# MicroMod_Processor_STM32WB5MMG.net
KiCad netlist of a schematic drawn in EAGLE
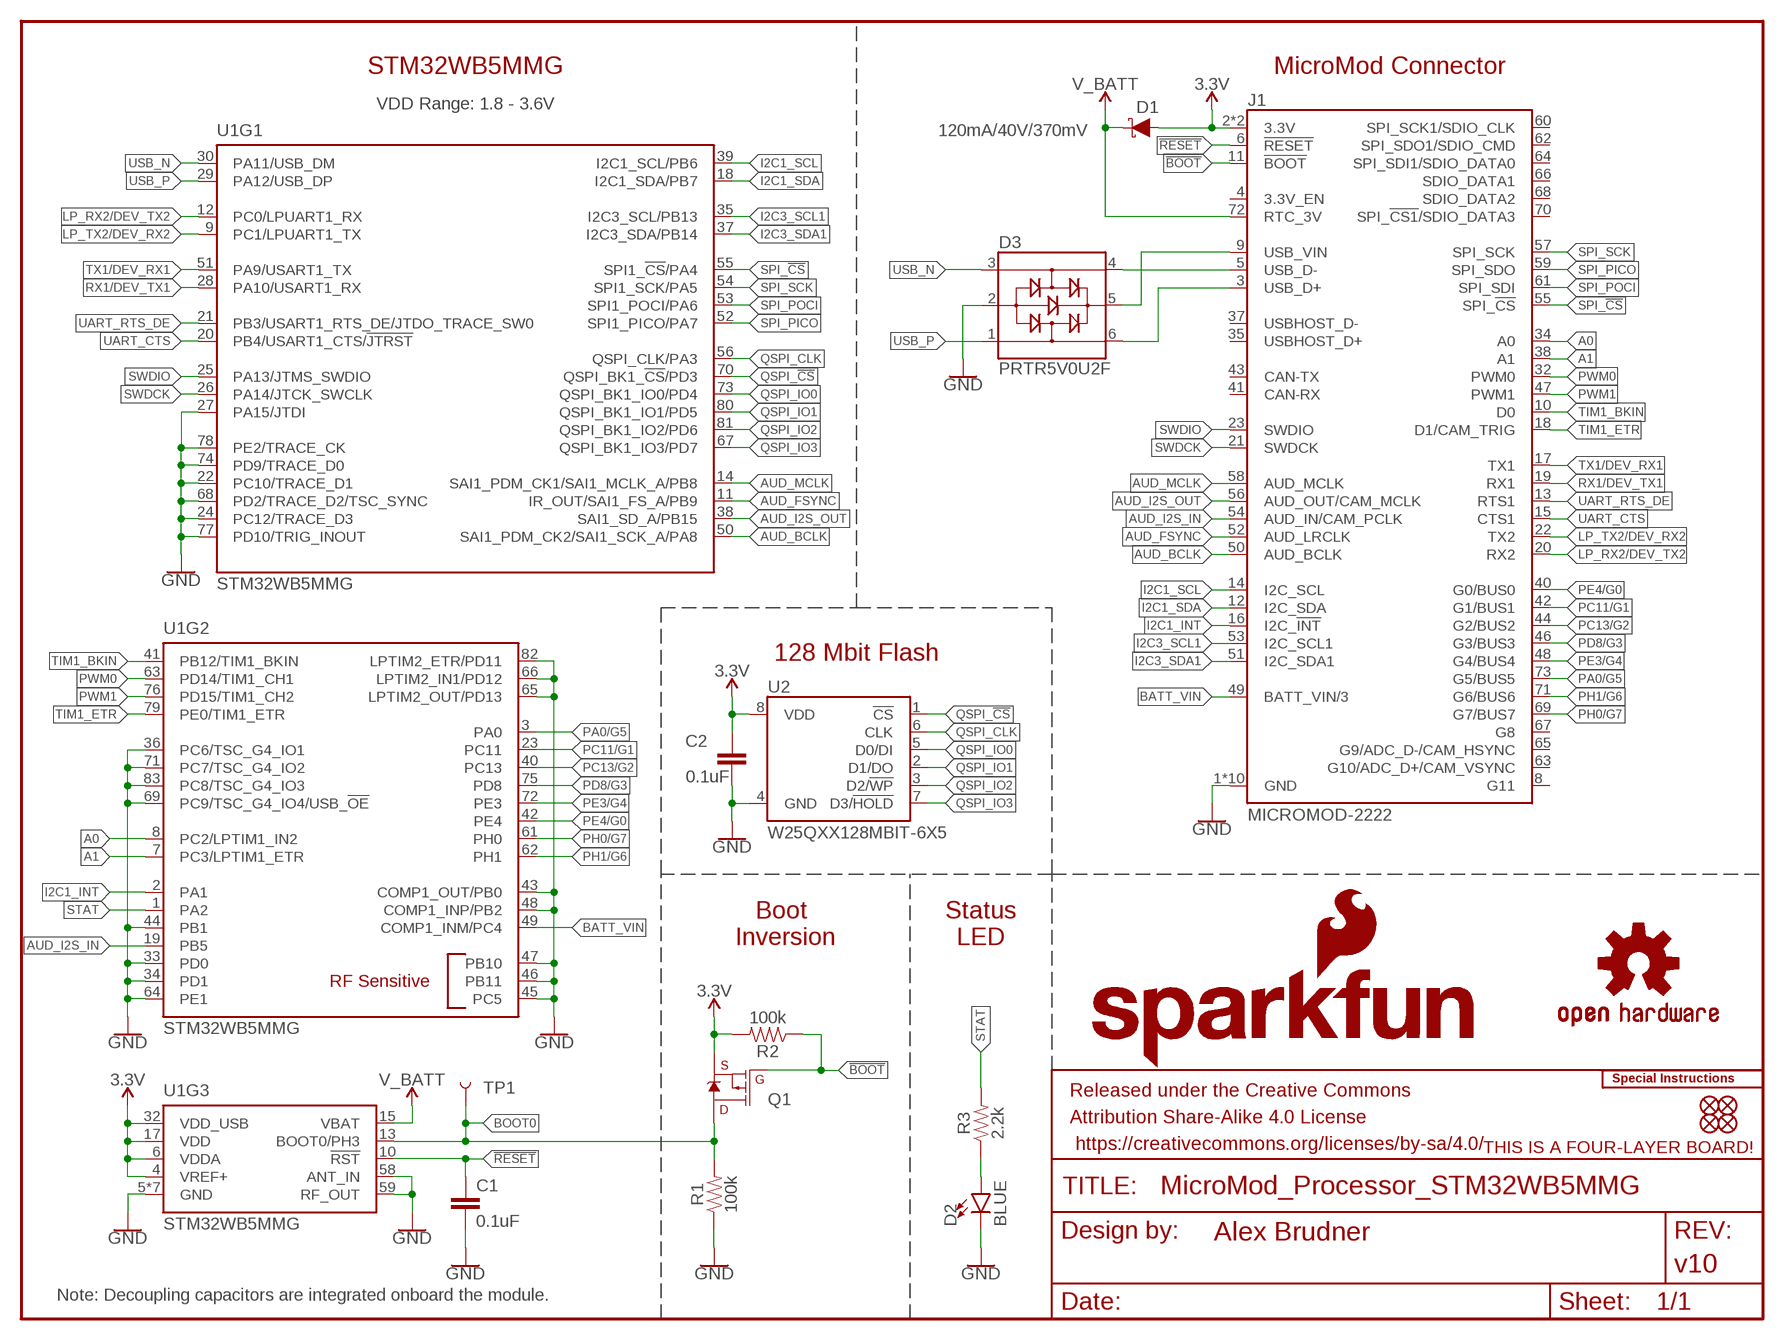
[diagram p0: schematic, sheet 1]

(export (version "E")
  (design (tool "Eeschema 10.0.6"))
  (components
    (comp (ref "C1")
      (value "0.1uF")
      (footprint "eagle-import:0402-TIGHT")
      (libsource (lib "eagle-import") (part "0.1UF-0402T-10V-10%-X7R"))
    )
    (comp (ref "C2")
      (value "0.1uF")
      (footprint "eagle-import:0402-TIGHT")
      (libsource (lib "eagle-import") (part "0.1UF-0402T-10V-10%-X7R"))
    )
    (comp (ref "D1")
      (value "120mA/40V/370mV")
      (footprint "eagle-import:SOD-523")
      (libsource (lib "eagle-import") (part "DIODE-SCHOTTKY-RB751S40"))
    )
    (comp (ref "D2")
      (value "BLUE")
      (footprint "eagle-import:LED-0603")
      (libsource (lib "eagle-import") (part "LED-BLUE0603"))
    )
    (comp (ref "D3")
      (value "PRTR5V0U2F")
      (footprint "eagle-import:SOT886")
      (libsource (lib "eagle-import") (part "PRTR5V0U2F"))
    )
    (comp (ref "FD1")
      (value "FIDUCIALUFIDUCIAL")
      (footprint "eagle-import:FIDUCIAL-MICRO")
      (libsource (lib "eagle-import") (part "FIDUCIALUFIDUCIAL"))
    )
    (comp (ref "FD2")
      (value "FIDUCIALUFIDUCIAL")
      (footprint "eagle-import:FIDUCIAL-MICRO")
      (libsource (lib "eagle-import") (part "FIDUCIALUFIDUCIAL"))
    )
    (comp (ref "FD3")
      (value "FIDUCIALUFIDUCIAL")
      (footprint "eagle-import:FIDUCIAL-MICRO")
      (libsource (lib "eagle-import") (part "FIDUCIALUFIDUCIAL"))
    )
    (comp (ref "FD4")
      (value "FIDUCIALUFIDUCIAL")
      (footprint "eagle-import:FIDUCIAL-MICRO")
      (libsource (lib "eagle-import") (part "FIDUCIALUFIDUCIAL"))
    )
    (comp (ref "FRAME2")
      (value "FRAME-LETTER")
      (footprint "eagle-import:CREATIVE_COMMONS")
      (fields (field (name "DESIGNER") "Alex Brudner") (field (name "REV") "v10"))
      (libsource (lib "eagle-import") (part "FRAME-LETTER"))
    )
    (comp (ref "J1")
      (value "MICROMOD-2222")
      (footprint "eagle-import:M.2-CARD-E-22")
      (libsource (lib "eagle-import") (part "MICROMOD-2222"))
    )
    (comp (ref "LOGO1")
      (value "FOUR_LAYER_WARNING")
      (footprint "eagle-import:FOUR_LAYER_WARNING")
      (libsource (lib "eagle-import") (part "FOUR_LAYER_WARNING"))
    )
    (comp (ref "LOGO2")
      (value "OSHW-LOGOMINI")
      (footprint "eagle-import:OSHW-LOGO-MINI")
      (libsource (lib "eagle-import") (part "OSHW-LOGOMINI"))
    )
    (comp (ref "LOGO3")
      (value "SFE_LOGO_NAME_FLAME.1_INCH")
      (footprint "eagle-import:SFE_LOGO_NAME_FLAME_.1")
      (libsource (lib "eagle-import") (part "SFE_LOGO_NAME_FLAME.1_INCH"))
    )
    (comp (ref "LOGO4")
      (value "SPECIAL_INSTRUCTIONS-ORDERING")
      (footprint "eagle-import:ORDERING_INSTRUCTIONS")
      (libsource (lib "eagle-import") (part "SPECIAL_INSTRUCTIONS-ORDERING"))
    )
    (comp (ref "Q1")
      (value "20V/4.2A/52mΩ/1.4W")
      (footprint "eagle-import:SOT23-3")
      (libsource (lib "eagle-import") (part "MOSFET_PCH-DMG2305UX-7"))
    )
    (comp (ref "R1")
      (value "100k")
      (footprint "eagle-import:0402-TIGHT")
      (libsource (lib "eagle-import") (part "100KOHM-0402T-1/16W-1%"))
    )
    (comp (ref "R2")
      (value "100k")
      (footprint "eagle-import:0402-TIGHT")
      (libsource (lib "eagle-import") (part "100KOHM-0402T-1/16W-1%"))
    )
    (comp (ref "R3")
      (value "2.2k")
      (footprint "eagle-import:0402-TIGHT")
      (libsource (lib "eagle-import") (part "2.2KOHM-0402T-1/16W-1%"))
    )
    (comp (ref "TP1")
      (value "TEST-POINT3")
      (footprint "eagle-import:PAD.03X.03")
      (libsource (lib "eagle-import") (part "TEST-POINT3"))
    )
    (comp (ref "U1")
      (value "STM32WB5MMG")
      (footprint "eagle-import:SIP-LGA86")
      (libsource (lib "eagle-import") (part "STM32WB5MMG_LOGICAL"))
    )
    (comp (ref "U2")
      (value "W25QXX128MBIT-6X5")
      (footprint "eagle-import:WSON-8-6X5")
      (libsource (lib "eagle-import") (part "W25QXX128MBIT-6X5"))
    )
  )
  (nets
    (net (code "1") (name "/QSPI_~{CS}") (class "Default")
      (node (ref "U1") (pin "70") (pinfunction "QSPI_BK1_~{CS}/PD3_70") (pintype "bidirectional"))
      (node (ref "U2") (pin "1") (pinfunction "~{CS}_1") (pintype "bidirectional"))
    )
    (net (code "2") (name "/SPI_~{CS}") (class "Default")
      (node (ref "J1") (pin "55") (pinfunction "SPI_~{CS}_55") (pintype "bidirectional"))
      (node (ref "U1") (pin "55") (pinfunction "SPI1_~{CS}/PA4_55") (pintype "bidirectional"))
    )
    (net (code "3") (name "/~{BOOT}") (class "Default")
      (node (ref "J1") (pin "11") (pinfunction "~{BOOT}_11") (pintype "bidirectional"))
      (node (ref "Q1") (pin "1") (pinfunction "G_1") (pintype "bidirectional"))
      (node (ref "R2") (pin "1") (pinfunction "1_1") (pintype "passive"))
    )
    (net (code "4") (name "/~{RESET}") (class "Default")
      (node (ref "C1") (pin "1") (pinfunction "1_1") (pintype "passive"))
      (node (ref "J1") (pin "6") (pinfunction "~{RESET}_6") (pintype "bidirectional"))
      (node (ref "U1") (pin "10") (pinfunction "~{RST}_10") (pintype "bidirectional"))
    )
    (net (code "5") (name "3.3V") (class "Default")
      (node (ref "C2") (pin "1") (pinfunction "1_1") (pintype "passive"))
      (node (ref "D1") (pin "A") (pinfunction "A_A") (pintype "passive"))
      (node (ref "J1") (pin "2") (pinfunction "3.3V_2") (pintype "bidirectional"))
      (node (ref "J1") (pin "74") (pinfunction "3.3V_74") (pintype "bidirectional"))
      (node (ref "Q1") (pin "2") (pinfunction "S_2") (pintype "bidirectional"))
      (node (ref "R2") (pin "2") (pinfunction "2_2") (pintype "passive"))
      (node (ref "U1") (pin "17") (pinfunction "VDD_17") (pintype "bidirectional"))
      (node (ref "U1") (pin "32") (pinfunction "VDD_USB_32") (pintype "bidirectional"))
      (node (ref "U1") (pin "4") (pinfunction "VREF+_4") (pintype "bidirectional"))
      (node (ref "U1") (pin "6") (pinfunction "VDDA_6") (pintype "bidirectional"))
      (node (ref "U2") (pin "8") (pinfunction "VDD_8") (pintype "bidirectional"))
    )
    (net (code "6") (name "A0") (class "Default")
      (node (ref "J1") (pin "34") (pinfunction "A0_34") (pintype "bidirectional"))
      (node (ref "U1") (pin "8") (pinfunction "PC2/LPTIM1_IN2_8") (pintype "bidirectional"))
    )
    (net (code "7") (name "A1") (class "Default")
      (node (ref "J1") (pin "38") (pinfunction "A1_38") (pintype "bidirectional"))
      (node (ref "U1") (pin "7") (pinfunction "PC3/LPTIM1_ETR_7") (pintype "bidirectional"))
    )
    (net (code "8") (name "AUD_BCLK") (class "Default")
      (node (ref "J1") (pin "50") (pinfunction "AUD_BCLK_50") (pintype "bidirectional"))
      (node (ref "U1") (pin "50") (pinfunction "SAI1_PDM_CK2/SAI1_SCK_A/PA8_50") (pintype "bidirectional"))
    )
    (net (code "9") (name "AUD_FSYNC") (class "Default")
      (node (ref "J1") (pin "52") (pinfunction "AUD_LRCLK_52") (pintype "bidirectional"))
      (node (ref "U1") (pin "11") (pinfunction "IR_OUT/SAI1_FS_A/PB9_11") (pintype "bidirectional"))
    )
    (net (code "10") (name "AUD_I2S_IN") (class "Default")
      (node (ref "J1") (pin "54") (pinfunction "AUD_IN/CAM_PCLK_54") (pintype "bidirectional"))
      (node (ref "U1") (pin "19") (pinfunction "PB5_19") (pintype "bidirectional"))
    )
    (net (code "11") (name "AUD_I2S_OUT") (class "Default")
      (node (ref "J1") (pin "56") (pinfunction "AUD_OUT/CAM_MCLK_56") (pintype "bidirectional"))
      (node (ref "U1") (pin "38") (pinfunction "SAI1_SD_A/PB15_38") (pintype "bidirectional"))
    )
    (net (code "12") (name "AUD_MCLK") (class "Default")
      (node (ref "J1") (pin "58") (pinfunction "AUD_MCLK_58") (pintype "bidirectional"))
      (node (ref "U1") (pin "14") (pinfunction "SAI1_PDM_CK1/SAI1_MCLK_A/PB8_14") (pintype "bidirectional"))
    )
    (net (code "13") (name "BATT_VIN") (class "Default")
      (node (ref "J1") (pin "49") (pinfunction "BATT_VIN/3_49") (pintype "bidirectional"))
      (node (ref "U1") (pin "49") (pinfunction "COMP1_INM/PC4_49") (pintype "bidirectional"))
    )
    (net (code "14") (name "BOOT0") (class "Default")
      (node (ref "Q1") (pin "3") (pinfunction "D_3") (pintype "bidirectional"))
      (node (ref "R1") (pin "2") (pinfunction "2_2") (pintype "passive"))
      (node (ref "TP1") (pin "1") (pinfunction "1_1") (pintype "bidirectional"))
      (node (ref "U1") (pin "13") (pinfunction "BOOT0/PH3_13") (pintype "bidirectional"))
    )
    (net (code "15") (name "GND") (class "Default")
      (node (ref "C1") (pin "2") (pinfunction "2_2") (pintype "passive"))
      (node (ref "C2") (pin "2") (pinfunction "2_2") (pintype "passive"))
      (node (ref "D2") (pin "C") (pinfunction "C_C") (pintype "passive"))
      (node (ref "D3") (pin "2") (pinfunction "2_2") (pintype "power_in"))
      (node (ref "J1") (pin "1") (pinfunction "GND_1") (pintype "bidirectional"))
      (node (ref "J1") (pin "33") (pinfunction "GND_33") (pintype "bidirectional"))
      (node (ref "J1") (pin "36") (pinfunction "GND_36") (pintype "bidirectional"))
      (node (ref "J1") (pin "39") (pinfunction "GND_39") (pintype "bidirectional"))
      (node (ref "J1") (pin "45") (pinfunction "GND_45") (pintype "bidirectional"))
      (node (ref "J1") (pin "7") (pinfunction "GND_7") (pintype "bidirectional"))
      (node (ref "J1") (pin "75") (pinfunction "GND_75") (pintype "bidirectional"))
      (node (ref "J1") (pin "GND1") (pinfunction "GND_GND1") (pintype "bidirectional"))
      (node (ref "J1") (pin "GND2") (pinfunction "GND_GND2") (pintype "bidirectional"))
      (node (ref "J1") (pin "GND3") (pinfunction "GND_GND3") (pintype "bidirectional"))
      (node (ref "R1") (pin "1") (pinfunction "1_1") (pintype "passive"))
      (node (ref "U1") (pin "16") (pinfunction "GND_16") (pintype "bidirectional"))
      (node (ref "U1") (pin "22") (pinfunction "PC10/TRACE_D1_22") (pintype "bidirectional"))
      (node (ref "U1") (pin "24") (pinfunction "PC12/TRACE_D3_24") (pintype "bidirectional"))
      (node (ref "U1") (pin "27") (pinfunction "PA15/JTDI_27") (pintype "bidirectional"))
      (node (ref "U1") (pin "31") (pinfunction "GND_31") (pintype "bidirectional"))
      (node (ref "U1") (pin "33") (pinfunction "PD0_33") (pintype "bidirectional"))
      (node (ref "U1") (pin "34") (pinfunction "PD1_34") (pintype "bidirectional"))
      (node (ref "U1") (pin "36") (pinfunction "PC6/TSC_G4_IO1_36") (pintype "bidirectional"))
      (node (ref "U1") (pin "43") (pinfunction "COMP1_OUT/PB0_43") (pintype "bidirectional"))
      (node (ref "U1") (pin "44") (pinfunction "PB1_44") (pintype "bidirectional"))
      (node (ref "U1") (pin "45") (pinfunction "PC5_45") (pintype "bidirectional"))
      (node (ref "U1") (pin "46") (pinfunction "PB11_46") (pintype "bidirectional"))
      (node (ref "U1") (pin "47") (pinfunction "PB10_47") (pintype "bidirectional"))
      (node (ref "U1") (pin "48") (pinfunction "COMP1_INP/PB2_48") (pintype "bidirectional"))
      (node (ref "U1") (pin "5") (pinfunction "GND_5") (pintype "bidirectional"))
      (node (ref "U1") (pin "57") (pinfunction "GND_57") (pintype "bidirectional"))
      (node (ref "U1") (pin "58") (pinfunction "ANT_IN_58") (pintype "bidirectional"))
      (node (ref "U1") (pin "59") (pinfunction "RF_OUT_59") (pintype "bidirectional"))
      (node (ref "U1") (pin "60") (pinfunction "GND_60") (pintype "bidirectional"))
      (node (ref "U1") (pin "64") (pinfunction "PE1_64") (pintype "bidirectional"))
      (node (ref "U1") (pin "65") (pinfunction "LPTIM2_OUT/PD13_65") (pintype "bidirectional"))
      (node (ref "U1") (pin "66") (pinfunction "LPTIM2_IN1/PD12_66") (pintype "bidirectional"))
      (node (ref "U1") (pin "68") (pinfunction "PD2/TRACE_D2/TSC_SYNC_68") (pintype "bidirectional"))
      (node (ref "U1") (pin "69") (pinfunction "PC9/TSC_G4_IO4/USB_~{OE}_69") (pintype "bidirectional"))
      (node (ref "U1") (pin "71") (pinfunction "PC7/TSC_G4_IO2_71") (pintype "bidirectional"))
      (node (ref "U1") (pin "74") (pinfunction "PD9/TRACE_D0_74") (pintype "bidirectional"))
      (node (ref "U1") (pin "77") (pinfunction "PD10/TRIG_INOUT_77") (pintype "bidirectional"))
      (node (ref "U1") (pin "78") (pinfunction "PE2/TRACE_CK_78") (pintype "bidirectional"))
      (node (ref "U1") (pin "82") (pinfunction "LPTIM2_ETR/PD11_82") (pintype "bidirectional"))
      (node (ref "U1") (pin "83") (pinfunction "PC8/TSC_G4_IO3_83") (pintype "bidirectional"))
      (node (ref "U1") (pin "84") (pinfunction "GND_84") (pintype "bidirectional"))
      (node (ref "U1") (pin "86") (pinfunction "GND_86") (pintype "bidirectional"))
      (node (ref "U2") (pin "4") (pinfunction "GND_4") (pintype "bidirectional"))
    )
    (net (code "16") (name "I2C1_INT") (class "Default")
      (node (ref "J1") (pin "16") (pinfunction "I2C_~{INT}_16") (pintype "bidirectional"))
      (node (ref "U1") (pin "2") (pinfunction "PA1_2") (pintype "bidirectional"))
    )
    (net (code "17") (name "I2C1_SCL") (class "Default")
      (node (ref "J1") (pin "14") (pinfunction "I2C_SCL_14") (pintype "bidirectional"))
      (node (ref "U1") (pin "39") (pinfunction "I2C1_SCL/PB6_39") (pintype "bidirectional"))
    )
    (net (code "18") (name "I2C1_SDA") (class "Default")
      (node (ref "J1") (pin "12") (pinfunction "I2C_SDA_12") (pintype "bidirectional"))
      (node (ref "U1") (pin "18") (pinfunction "I2C1_SDA/PB7_18") (pintype "bidirectional"))
    )
    (net (code "19") (name "I2C3_SCL1") (class "Default")
      (node (ref "J1") (pin "53") (pinfunction "I2C_SCL1_53") (pintype "bidirectional"))
      (node (ref "U1") (pin "35") (pinfunction "I2C3_SCL/PB13_35") (pintype "bidirectional"))
    )
    (net (code "20") (name "I2C3_SDA1") (class "Default")
      (node (ref "J1") (pin "51") (pinfunction "I2C_SDA1_51") (pintype "bidirectional"))
      (node (ref "U1") (pin "37") (pinfunction "I2C3_SDA/PB14_37") (pintype "bidirectional"))
    )
    (net (code "21") (name "LP_RX2{slash}DEV_TX2") (class "Default")
      (node (ref "J1") (pin "20") (pinfunction "RX2_20") (pintype "bidirectional"))
      (node (ref "U1") (pin "12") (pinfunction "PC0/LPUART1_RX_12") (pintype "bidirectional"))
    )
    (net (code "22") (name "LP_TX2{slash}DEV_RX2") (class "Default")
      (node (ref "J1") (pin "22") (pinfunction "TX2_22") (pintype "bidirectional"))
      (node (ref "U1") (pin "9") (pinfunction "PC1/LPUART1_TX_9") (pintype "bidirectional"))
    )
    (net (code "23") (name "Net-(D2-PadA)") (class "Default")
      (node (ref "D2") (pin "A") (pinfunction "A_A") (pintype "passive"))
      (node (ref "R3") (pin "1") (pinfunction "1_1") (pintype "passive"))
    )
    (net (code "24") (name "Net-(J1-USB_D+)") (class "Default")
      (node (ref "D3") (pin "6") (pinfunction "6_6") (pintype "bidirectional"))
      (node (ref "J1") (pin "3") (pinfunction "USB_D+_3") (pintype "bidirectional"))
    )
    (net (code "25") (name "Net-(J1-USB_D-)") (class "Default")
      (node (ref "D3") (pin "4") (pinfunction "4_4") (pintype "bidirectional"))
      (node (ref "J1") (pin "5") (pinfunction "USB_D-_5") (pintype "bidirectional"))
    )
    (net (code "26") (name "Net-(J1-USB_VIN)") (class "Default")
      (node (ref "D3") (pin "5") (pinfunction "5_5") (pintype "power_in"))
      (node (ref "J1") (pin "9") (pinfunction "USB_VIN_9") (pintype "bidirectional"))
    )
    (net (code "27") (name "PA0{slash}G5") (class "Default")
      (node (ref "J1") (pin "73") (pinfunction "G5/BUS5_73") (pintype "bidirectional"))
      (node (ref "U1") (pin "3") (pinfunction "PA0_3") (pintype "bidirectional"))
    )
    (net (code "28") (name "PC11{slash}G1") (class "Default")
      (node (ref "J1") (pin "42") (pinfunction "G1/BUS1_42") (pintype "bidirectional"))
      (node (ref "U1") (pin "23") (pinfunction "PC11_23") (pintype "bidirectional"))
    )
    (net (code "29") (name "PC13{slash}G2") (class "Default")
      (node (ref "J1") (pin "44") (pinfunction "G2/BUS2_44") (pintype "bidirectional"))
      (node (ref "U1") (pin "40") (pinfunction "PC13_40") (pintype "bidirectional"))
    )
    (net (code "30") (name "PD8{slash}G3") (class "Default")
      (node (ref "J1") (pin "46") (pinfunction "G3/BUS3_46") (pintype "bidirectional"))
      (node (ref "U1") (pin "75") (pinfunction "PD8_75") (pintype "bidirectional"))
    )
    (net (code "31") (name "PE3{slash}G4") (class "Default")
      (node (ref "J1") (pin "48") (pinfunction "G4/BUS4_48") (pintype "bidirectional"))
      (node (ref "U1") (pin "72") (pinfunction "PE3_72") (pintype "bidirectional"))
    )
    (net (code "32") (name "PE4{slash}G0") (class "Default")
      (node (ref "J1") (pin "40") (pinfunction "G0/BUS0_40") (pintype "bidirectional"))
      (node (ref "U1") (pin "42") (pinfunction "PE4_42") (pintype "bidirectional"))
    )
    (net (code "33") (name "PH0{slash}G7") (class "Default")
      (node (ref "J1") (pin "69") (pinfunction "G7/BUS7_69") (pintype "bidirectional"))
      (node (ref "U1") (pin "61") (pinfunction "PH0_61") (pintype "bidirectional"))
    )
    (net (code "34") (name "PH1{slash}G6") (class "Default")
      (node (ref "J1") (pin "71") (pinfunction "G6/BUS6_71") (pintype "bidirectional"))
      (node (ref "U1") (pin "62") (pinfunction "PH1_62") (pintype "bidirectional"))
    )
    (net (code "35") (name "PWM0") (class "Default")
      (node (ref "J1") (pin "32") (pinfunction "PWM0_32") (pintype "bidirectional"))
      (node (ref "U1") (pin "63") (pinfunction "PD14/TIM1_CH1_63") (pintype "bidirectional"))
    )
    (net (code "36") (name "PWM1") (class "Default")
      (node (ref "J1") (pin "47") (pinfunction "PWM1_47") (pintype "bidirectional"))
      (node (ref "U1") (pin "76") (pinfunction "PD15/TIM1_CH2_76") (pintype "bidirectional"))
    )
    (net (code "37") (name "QSPI_CLK") (class "Default")
      (node (ref "U1") (pin "56") (pinfunction "QSPI_CLK/PA3_56") (pintype "bidirectional"))
      (node (ref "U2") (pin "6") (pinfunction "CLK_6") (pintype "bidirectional"))
    )
    (net (code "38") (name "QSPI_IO0") (class "Default")
      (node (ref "U1") (pin "73") (pinfunction "QSPI_BK1_IO0/PD4_73") (pintype "bidirectional"))
      (node (ref "U2") (pin "5") (pinfunction "D0/DI_5") (pintype "bidirectional"))
    )
    (net (code "39") (name "QSPI_IO1") (class "Default")
      (node (ref "U1") (pin "80") (pinfunction "QSPI_BK1_IO1/PD5_80") (pintype "bidirectional"))
      (node (ref "U2") (pin "2") (pinfunction "D1/DO_2") (pintype "bidirectional"))
    )
    (net (code "40") (name "QSPI_IO2") (class "Default")
      (node (ref "U1") (pin "81") (pinfunction "QSPI_BK1_IO2/PD6_81") (pintype "bidirectional"))
      (node (ref "U2") (pin "3") (pinfunction "D2/~{WP}_3") (pintype "bidirectional"))
    )
    (net (code "41") (name "QSPI_IO3") (class "Default")
      (node (ref "U1") (pin "67") (pinfunction "QSPI_BK1_IO3/PD7_67") (pintype "bidirectional"))
      (node (ref "U2") (pin "7") (pinfunction "D3/~{HOLD}_7") (pintype "bidirectional"))
    )
    (net (code "42") (name "RX1{slash}DEV_TX1") (class "Default")
      (node (ref "J1") (pin "19") (pinfunction "RX1_19") (pintype "bidirectional"))
      (node (ref "U1") (pin "28") (pinfunction "PA10/USART1_RX_28") (pintype "bidirectional"))
    )
    (net (code "43") (name "SPI_PICO") (class "Default")
      (node (ref "J1") (pin "59") (pinfunction "SPI_SDO_59") (pintype "bidirectional"))
      (node (ref "U1") (pin "52") (pinfunction "SPI1_PICO/PA7_52") (pintype "bidirectional"))
    )
    (net (code "44") (name "SPI_POCI") (class "Default")
      (node (ref "J1") (pin "61") (pinfunction "SPI_SDI_61") (pintype "bidirectional"))
      (node (ref "U1") (pin "53") (pinfunction "SPI1_POCI/PA6_53") (pintype "bidirectional"))
    )
    (net (code "45") (name "SPI_SCK") (class "Default")
      (node (ref "J1") (pin "57") (pinfunction "SPI_SCK_57") (pintype "bidirectional"))
      (node (ref "U1") (pin "54") (pinfunction "SPI1_SCK/PA5_54") (pintype "bidirectional"))
    )
    (net (code "46") (name "STAT") (class "Default")
      (node (ref "R3") (pin "2") (pinfunction "2_2") (pintype "passive"))
      (node (ref "U1") (pin "1") (pinfunction "PA2_1") (pintype "bidirectional"))
    )
    (net (code "47") (name "SWDCK") (class "Default")
      (node (ref "J1") (pin "21") (pinfunction "SWDCK_21") (pintype "bidirectional"))
      (node (ref "U1") (pin "26") (pinfunction "PA14/JTCK_SWCLK_26") (pintype "bidirectional"))
    )
    (net (code "48") (name "SWDIO") (class "Default")
      (node (ref "J1") (pin "23") (pinfunction "SWDIO_23") (pintype "bidirectional"))
      (node (ref "U1") (pin "25") (pinfunction "PA13/JTMS_SWDIO_25") (pintype "bidirectional"))
    )
    (net (code "49") (name "TIM1_BKIN") (class "Default")
      (node (ref "J1") (pin "10") (pinfunction "D0_10") (pintype "bidirectional"))
      (node (ref "U1") (pin "41") (pinfunction "PB12/TIM1_BKIN_41") (pintype "bidirectional"))
    )
    (net (code "50") (name "TIM1_ETR") (class "Default")
      (node (ref "J1") (pin "18") (pinfunction "D1/CAM_TRIG_18") (pintype "bidirectional"))
      (node (ref "U1") (pin "79") (pinfunction "PE0/TIM1_ETR_79") (pintype "bidirectional"))
    )
    (net (code "51") (name "TX1{slash}DEV_RX1") (class "Default")
      (node (ref "J1") (pin "17") (pinfunction "TX1_17") (pintype "bidirectional"))
      (node (ref "U1") (pin "51") (pinfunction "PA9/USART1_TX_51") (pintype "bidirectional"))
    )
    (net (code "52") (name "UART_CTS") (class "Default")
      (node (ref "J1") (pin "15") (pinfunction "CTS1_15") (pintype "bidirectional"))
      (node (ref "U1") (pin "20") (pinfunction "PB4/USART1_CTS/~{JTRST}_20") (pintype "bidirectional"))
    )
    (net (code "53") (name "UART_RTS_DE") (class "Default")
      (node (ref "J1") (pin "13") (pinfunction "RTS1_13") (pintype "bidirectional"))
      (node (ref "U1") (pin "21") (pinfunction "PB3/USART1_RTS_DE/JTDO_TRACE_SW0_21") (pintype "bidirectional"))
    )
    (net (code "54") (name "USB_N") (class "Default")
      (node (ref "D3") (pin "3") (pinfunction "3_3") (pintype "bidirectional"))
      (node (ref "U1") (pin "30") (pinfunction "PA11/USB_DM_30") (pintype "bidirectional"))
    )
    (net (code "55") (name "USB_P") (class "Default")
      (node (ref "D3") (pin "1") (pinfunction "1_1") (pintype "bidirectional"))
      (node (ref "U1") (pin "29") (pinfunction "PA12/USB_DP_29") (pintype "bidirectional"))
    )
    (net (code "56") (name "V_BATT") (class "Default")
      (node (ref "D1") (pin "C") (pinfunction "C_C") (pintype "passive"))
      (node (ref "J1") (pin "72") (pinfunction "RTC_3V_72") (pintype "bidirectional"))
      (node (ref "U1") (pin "15") (pinfunction "VBAT_15") (pintype "bidirectional"))
    )
    (net (code "57") (name "unconnected-(J1-3.3V_EN-Pad4)") (class "Default")
      (node (ref "J1") (pin "4") (pinfunction "3.3V_EN_4") (pintype "bidirectional"))
    )
    (net (code "58") (name "unconnected-(J1-CAN-RX-Pad41)") (class "Default")
      (node (ref "J1") (pin "41") (pinfunction "CAN-RX_41") (pintype "bidirectional"))
    )
    (net (code "59") (name "unconnected-(J1-CAN-TX-Pad43)") (class "Default")
      (node (ref "J1") (pin "43") (pinfunction "CAN-TX_43") (pintype "bidirectional"))
    )
    (net (code "60") (name "unconnected-(J1-G8-Pad67)") (class "Default")
      (node (ref "J1") (pin "67") (pinfunction "G8_67") (pintype "bidirectional"))
    )
    (net (code "61") (name "unconnected-(J1-G9{slash}ADC_D-{slash}CAM_HSYNC-Pad65)") (class "Default")
      (node (ref "J1") (pin "65") (pinfunction "G9/ADC_D-/CAM_HSYNC_65") (pintype "bidirectional"))
    )
    (net (code "62") (name "unconnected-(J1-G10{slash}ADC_D+{slash}CAM_VSYNC-Pad63)") (class "Default")
      (node (ref "J1") (pin "63") (pinfunction "G10/ADC_D+/CAM_VSYNC_63") (pintype "bidirectional"))
    )
    (net (code "63") (name "unconnected-(J1-G11-Pad8)") (class "Default")
      (node (ref "J1") (pin "8") (pinfunction "G11_8") (pintype "bidirectional"))
    )
    (net (code "64") (name "unconnected-(J1-SDIO_DATA1-Pad66)") (class "Default")
      (node (ref "J1") (pin "66") (pinfunction "SDIO_DATA1_66") (pintype "bidirectional"))
    )
    (net (code "65") (name "unconnected-(J1-SDIO_DATA2-Pad68)") (class "Default")
      (node (ref "J1") (pin "68") (pinfunction "SDIO_DATA2_68") (pintype "bidirectional"))
    )
    (net (code "66") (name "unconnected-(J1-SPI_SCK1{slash}SDIO_CLK-Pad60)") (class "Default")
      (node (ref "J1") (pin "60") (pinfunction "SPI_SCK1/SDIO_CLK_60") (pintype "bidirectional"))
    )
    (net (code "67") (name "unconnected-(J1-SPI_SDI1{slash}SDIO_DATA0-Pad64)") (class "Default")
      (node (ref "J1") (pin "64") (pinfunction "SPI_SDI1/SDIO_DATA0_64") (pintype "bidirectional"))
    )
    (net (code "68") (name "unconnected-(J1-SPI_SDO1{slash}SDIO_CMD-Pad62)") (class "Default")
      (node (ref "J1") (pin "62") (pinfunction "SPI_SDO1/SDIO_CMD_62") (pintype "bidirectional"))
    )
    (net (code "69") (name "unconnected-(J1-SPI_~{CS1}{slash}SDIO_DATA3-Pad70)") (class "Default")
      (node (ref "J1") (pin "70") (pinfunction "SPI_~{CS1}/SDIO_DATA3_70") (pintype "bidirectional"))
    )
    (net (code "70") (name "unconnected-(J1-USBHOST_D+-Pad35)") (class "Default")
      (node (ref "J1") (pin "35") (pinfunction "USBHOST_D+_35") (pintype "bidirectional"))
    )
    (net (code "71") (name "unconnected-(J1-USBHOST_D--Pad37)") (class "Default")
      (node (ref "J1") (pin "37") (pinfunction "USBHOST_D-_37") (pintype "bidirectional"))
    )
  )
)
